# wemos_rfmaster7x.net
KiCad netlist of a schematic drawn in EAGLE
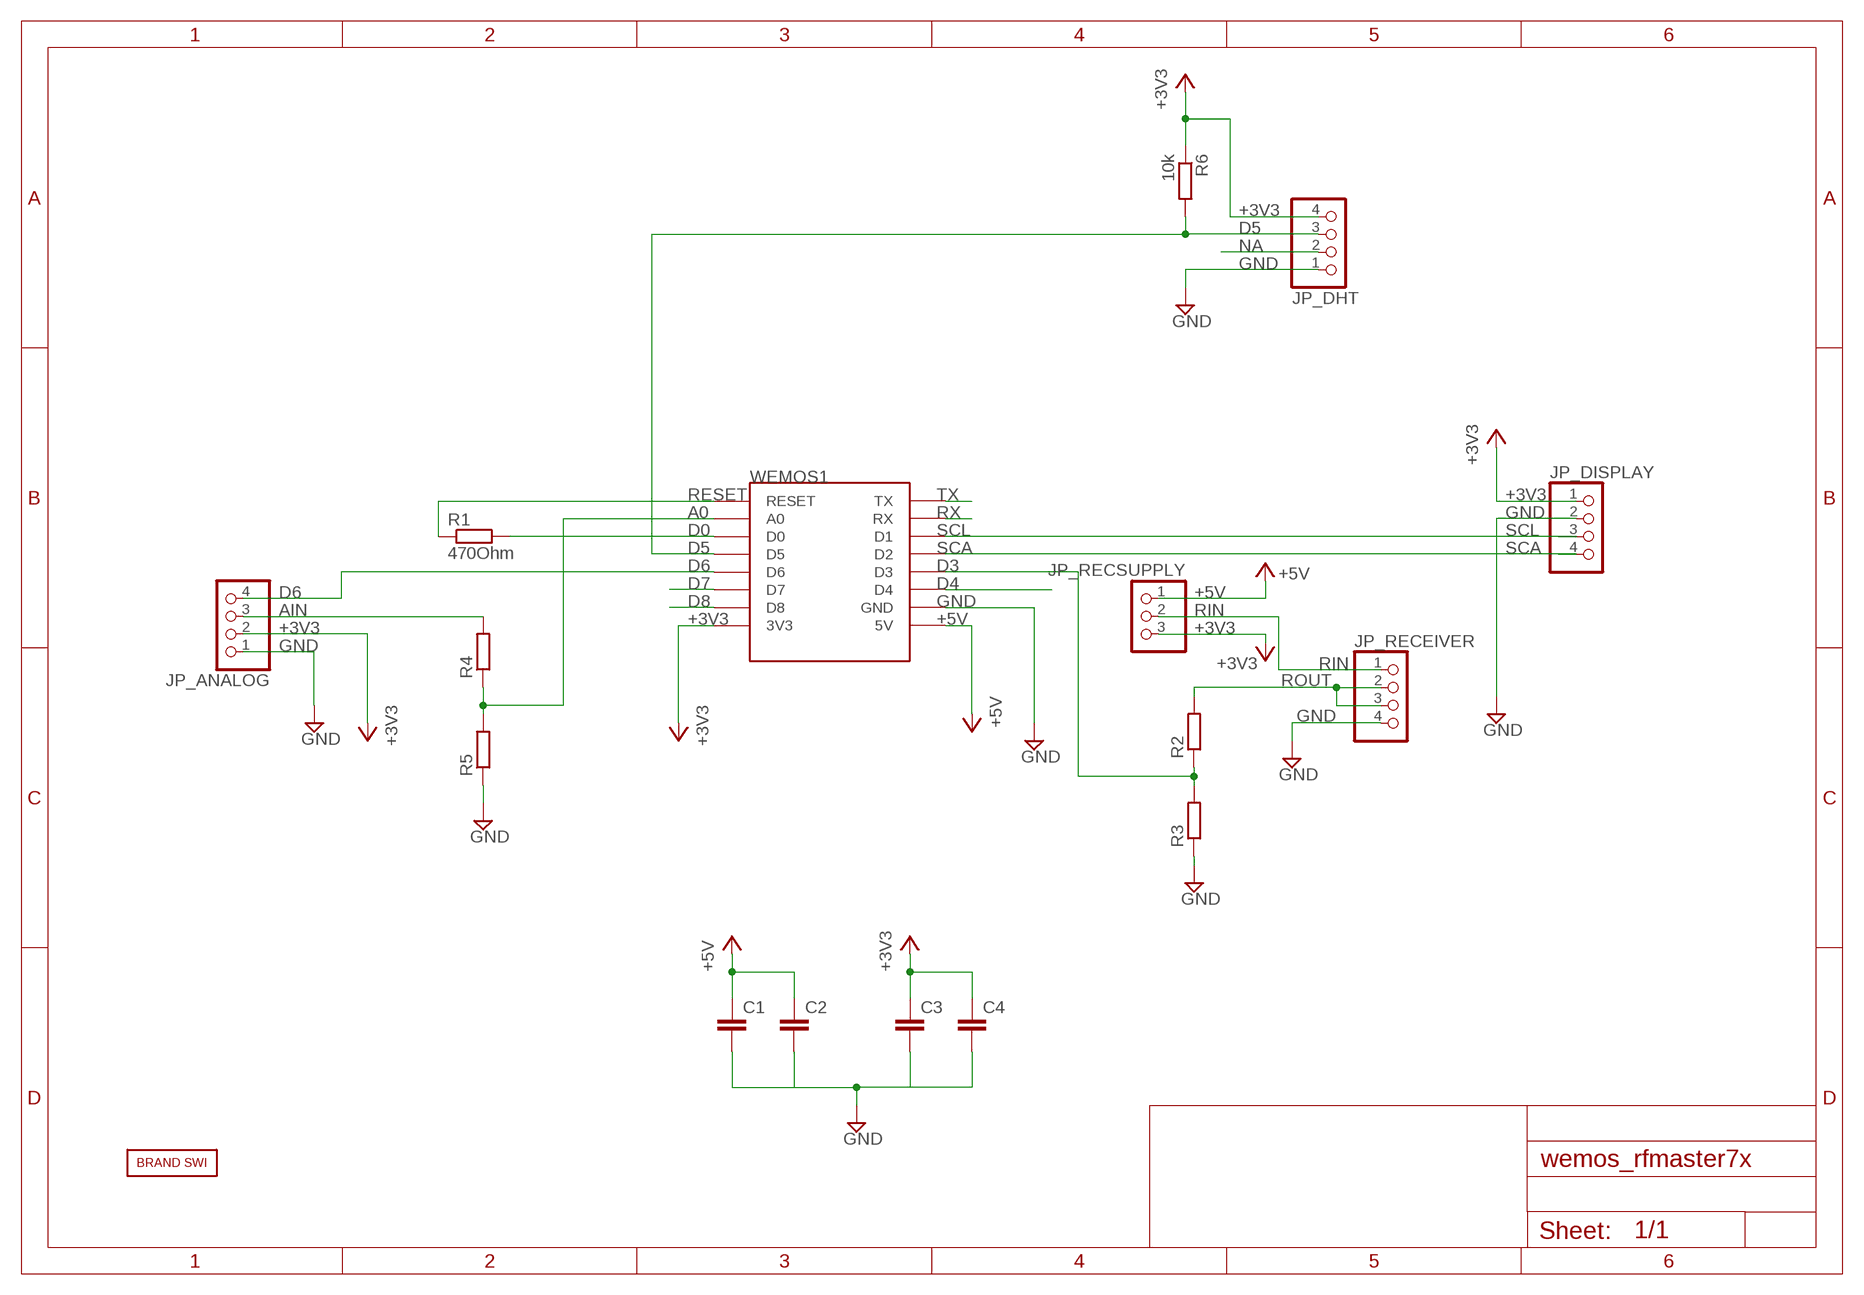
[diagram p0: schematic, sheet 1]

(export (version "E")
  (design (tool "Eeschema 10.0.6"))
  (components
    (comp (ref "C1")
      (value "C-EUC1210")
      (footprint "eagle-import:C1210")
      (libsource (lib "eagle-import") (part "C-EUC1210"))
    )
    (comp (ref "C2")
      (value "C-EUC1210")
      (footprint "eagle-import:C1210")
      (libsource (lib "eagle-import") (part "C-EUC1210"))
    )
    (comp (ref "C3")
      (value "C-EUC1210")
      (footprint "eagle-import:C1210")
      (libsource (lib "eagle-import") (part "C-EUC1210"))
    )
    (comp (ref "C4")
      (value "C-EUC1210")
      (footprint "eagle-import:C1210")
      (libsource (lib "eagle-import") (part "C-EUC1210"))
    )
    (comp (ref "JP_ANALOG")
      (value "PINHD-1X4")
      (footprint "eagle-import:1X04")
      (libsource (lib "eagle-import") (part "PINHD-1X4"))
    )
    (comp (ref "JP_DHT")
      (value "PINHD-1X4")
      (footprint "eagle-import:1X04")
      (libsource (lib "eagle-import") (part "pinhead@1_PINHD-1X4"))
    )
    (comp (ref "JP_DISPLAY")
      (value "PINHD-1X4")
      (footprint "eagle-import:1X04")
      (libsource (lib "eagle-import") (part "PINHD-1X4"))
    )
    (comp (ref "JP_RECEIVER")
      (value "PINHD-1X4")
      (footprint "eagle-import:1X04")
      (libsource (lib "eagle-import") (part "PINHD-1X4"))
    )
    (comp (ref "JP_RECSUPPLY")
      (value "PINHD-1X3")
      (footprint "eagle-import:1X03")
      (libsource (lib "eagle-import") (part "PINHD-1X3"))
    )
    (comp (ref "R1")
      (value "470Ohm")
      (footprint "eagle-import:R0805")
      (libsource (lib "eagle-import") (part "R-EU_R0805"))
    )
    (comp (ref "R2")
      (value "R-EU_R0805")
      (footprint "eagle-import:R0805")
      (libsource (lib "eagle-import") (part "R-EU_R0805"))
    )
    (comp (ref "R3")
      (value "R-EU_R0805")
      (footprint "eagle-import:R0805")
      (libsource (lib "eagle-import") (part "R-EU_R0805"))
    )
    (comp (ref "R4")
      (value "R-EU_R0805")
      (footprint "eagle-import:R0805")
      (libsource (lib "eagle-import") (part "R-EU_R0805"))
    )
    (comp (ref "R5")
      (value "R-EU_R0805")
      (footprint "eagle-import:R0805")
      (libsource (lib "eagle-import") (part "R-EU_R0805"))
    )
    (comp (ref "R6")
      (value "10k")
      (footprint "eagle-import:R0805")
      (libsource (lib "eagle-import") (part "R-EU_R0805"))
    )
    (comp (ref "U$2")
      (value "BRAND_SWI5X7")
      (footprint "eagle-import:BRAND_SWI_5X7")
      (libsource (lib "eagle-import") (part "BRAND_SWI5X7"))
    )
    (comp (ref "WEMOS1")
      (value "WEMOS-D1-MINI")
      (footprint "eagle-import:WEMOS-D1-MINI")
      (libsource (lib "eagle-import") (part "WEMOS-D1-MINI"))
    )
  )
  (nets
    (net (code "1") (name "+3V3") (class "Default")
      (node (ref "C3") (pin "1") (pinfunction "1_1") (pintype "passive"))
      (node (ref "C4") (pin "1") (pinfunction "1_1") (pintype "passive"))
      (node (ref "JP_ANALOG") (pin "2") (pinfunction "2_2") (pintype "passive"))
      (node (ref "JP_DHT") (pin "4") (pinfunction "4_4") (pintype "passive"))
      (node (ref "JP_DISPLAY") (pin "1") (pinfunction "1_1") (pintype "passive"))
      (node (ref "JP_RECSUPPLY") (pin "3") (pinfunction "3_3") (pintype "passive"))
      (node (ref "R6") (pin "1") (pinfunction "1_1") (pintype "passive"))
      (node (ref "WEMOS1") (pin "3V3") (pinfunction "3V3_3V3") (pintype "bidirectional"))
    )
    (net (code "2") (name "+5V") (class "Default")
      (node (ref "C1") (pin "1") (pinfunction "1_1") (pintype "passive"))
      (node (ref "C2") (pin "1") (pinfunction "1_1") (pintype "passive"))
      (node (ref "JP_RECSUPPLY") (pin "1") (pinfunction "1_1") (pintype "passive"))
      (node (ref "WEMOS1") (pin "5V") (pinfunction "5V_5V") (pintype "bidirectional"))
    )
    (net (code "3") (name "/A0") (class "Default")
      (node (ref "R4") (pin "1") (pinfunction "1_1") (pintype "passive"))
      (node (ref "R5") (pin "2") (pinfunction "2_2") (pintype "passive"))
      (node (ref "WEMOS1") (pin "A0") (pinfunction "A0_A0") (pintype "bidirectional"))
    )
    (net (code "4") (name "/AIN") (class "Default")
      (node (ref "JP_ANALOG") (pin "3") (pinfunction "3_3") (pintype "passive"))
      (node (ref "R4") (pin "2") (pinfunction "2_2") (pintype "passive"))
    )
    (net (code "5") (name "/D0") (class "Default")
      (node (ref "R1") (pin "2") (pinfunction "2_2") (pintype "passive"))
      (node (ref "WEMOS1") (pin "D0") (pinfunction "D0_D0") (pintype "bidirectional"))
    )
    (net (code "6") (name "/D3") (class "Default")
      (node (ref "R2") (pin "1") (pinfunction "1_1") (pintype "passive"))
      (node (ref "R3") (pin "2") (pinfunction "2_2") (pintype "passive"))
      (node (ref "WEMOS1") (pin "D3") (pinfunction "D3_D3") (pintype "bidirectional"))
    )
    (net (code "7") (name "/D4") (class "Default")
      (node (ref "WEMOS1") (pin "D4") (pinfunction "D4_D4") (pintype "bidirectional"))
    )
    (net (code "8") (name "/D5") (class "Default")
      (node (ref "JP_DHT") (pin "3") (pinfunction "3_3") (pintype "passive"))
      (node (ref "R6") (pin "2") (pinfunction "2_2") (pintype "passive"))
      (node (ref "WEMOS1") (pin "D5") (pinfunction "D5_D5") (pintype "bidirectional"))
    )
    (net (code "9") (name "/D6") (class "Default")
      (node (ref "JP_ANALOG") (pin "4") (pinfunction "4_4") (pintype "passive"))
      (node (ref "WEMOS1") (pin "D6") (pinfunction "D6_D6") (pintype "bidirectional"))
    )
    (net (code "10") (name "/D7") (class "Default")
      (node (ref "WEMOS1") (pin "D7") (pinfunction "D7_D7") (pintype "bidirectional"))
    )
    (net (code "11") (name "/D8") (class "Default")
      (node (ref "WEMOS1") (pin "D8") (pinfunction "D8_D8") (pintype "bidirectional"))
    )
    (net (code "12") (name "/NA") (class "Default")
      (node (ref "JP_DHT") (pin "2") (pinfunction "2_2") (pintype "passive"))
    )
    (net (code "13") (name "/RESET") (class "Default")
      (node (ref "R1") (pin "1") (pinfunction "1_1") (pintype "passive"))
      (node (ref "WEMOS1") (pin "RESET") (pinfunction "RESET_RESET") (pintype "bidirectional"))
    )
    (net (code "14") (name "/RIN") (class "Default")
      (node (ref "JP_RECEIVER") (pin "1") (pinfunction "1_1") (pintype "passive"))
      (node (ref "JP_RECSUPPLY") (pin "2") (pinfunction "2_2") (pintype "passive"))
    )
    (net (code "15") (name "/ROUT") (class "Default")
      (node (ref "JP_RECEIVER") (pin "2") (pinfunction "2_2") (pintype "passive"))
      (node (ref "JP_RECEIVER") (pin "3") (pinfunction "3_3") (pintype "passive"))
      (node (ref "R2") (pin "2") (pinfunction "2_2") (pintype "passive"))
    )
    (net (code "16") (name "/RX") (class "Default")
      (node (ref "WEMOS1") (pin "RX") (pinfunction "RX_RX") (pintype "bidirectional"))
    )
    (net (code "17") (name "/SCA") (class "Default")
      (node (ref "JP_DISPLAY") (pin "4") (pinfunction "4_4") (pintype "passive"))
      (node (ref "WEMOS1") (pin "D2") (pinfunction "D2_D2") (pintype "bidirectional"))
    )
    (net (code "18") (name "/SCL") (class "Default")
      (node (ref "JP_DISPLAY") (pin "3") (pinfunction "3_3") (pintype "passive"))
      (node (ref "WEMOS1") (pin "D1") (pinfunction "D1_D1") (pintype "bidirectional"))
    )
    (net (code "19") (name "/TX") (class "Default")
      (node (ref "WEMOS1") (pin "TX") (pinfunction "TX_TX") (pintype "bidirectional"))
    )
    (net (code "20") (name "GND") (class "Default")
      (node (ref "C1") (pin "2") (pinfunction "2_2") (pintype "passive"))
      (node (ref "C2") (pin "2") (pinfunction "2_2") (pintype "passive"))
      (node (ref "C3") (pin "2") (pinfunction "2_2") (pintype "passive"))
      (node (ref "C4") (pin "2") (pinfunction "2_2") (pintype "passive"))
      (node (ref "JP_ANALOG") (pin "1") (pinfunction "1_1") (pintype "passive"))
      (node (ref "JP_DHT") (pin "1") (pinfunction "1_1") (pintype "passive"))
      (node (ref "JP_DISPLAY") (pin "2") (pinfunction "2_2") (pintype "passive"))
      (node (ref "JP_RECEIVER") (pin "4") (pinfunction "4_4") (pintype "passive"))
      (node (ref "R3") (pin "1") (pinfunction "1_1") (pintype "passive"))
      (node (ref "R5") (pin "1") (pinfunction "1_1") (pintype "passive"))
      (node (ref "WEMOS1") (pin "GND") (pinfunction "GND_GND") (pintype "bidirectional"))
    )
  )
)
